# Joy2PS2_Adapter.net
KiCad netlist of a schematic drawn in EAGLE
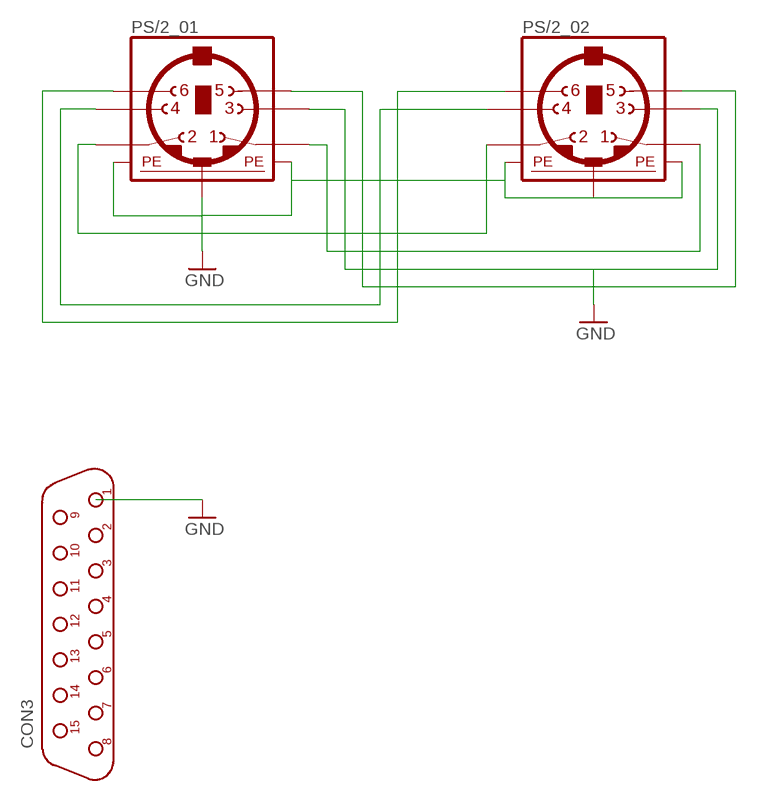
[diagram p0: schematic, sheet 1]

(export (version "E")
  (design (tool "Eeschema 10.0.6"))
  (components
    (comp (ref "CON3")
      (value "DB15F/90")
      (footprint "eagle-import:D-15F_90")
      (libsource (lib "eagle-import") (part "DB15F/90"))
    )
    (comp (ref "PS/2_01")
      (value "MINI_DIN_6")
      (footprint "eagle-import:M_DIN6")
      (libsource (lib "eagle-import") (part "MINI_DIN_6"))
    )
    (comp (ref "PS/2_02")
      (value "MINI_DIN_6")
      (footprint "eagle-import:M_DIN6")
      (libsource (lib "eagle-import") (part "MINI_DIN_6"))
    )
  )
  (nets
    (net (code "1") (name "GND") (class "Default")
      (node (ref "CON3") (pin "1") (pinfunction "1_1") (pintype "passive"))
      (node (ref "PS/2_01") (pin "3") (pinfunction "3_3") (pintype "passive"))
      (node (ref "PS/2_01") (pin "SH1") (pinfunction "PE1_SH1") (pintype "power_in"))
      (node (ref "PS/2_01") (pin "SH2") (pinfunction "PE2_SH2") (pintype "power_in"))
      (node (ref "PS/2_01") (pin "SH3") (pinfunction "PE3_SH3") (pintype "power_in"))
      (node (ref "PS/2_02") (pin "3") (pinfunction "3_3") (pintype "passive"))
      (node (ref "PS/2_02") (pin "SH1") (pinfunction "PE1_SH1") (pintype "power_in"))
      (node (ref "PS/2_02") (pin "SH2") (pinfunction "PE2_SH2") (pintype "power_in"))
      (node (ref "PS/2_02") (pin "SH3") (pinfunction "PE3_SH3") (pintype "power_in"))
    )
    (net (code "2") (name "Net-(PS/2_01-Pad1)") (class "Default")
      (node (ref "PS/2_01") (pin "1") (pinfunction "1_1") (pintype "passive"))
      (node (ref "PS/2_02") (pin "1") (pinfunction "1_1") (pintype "passive"))
    )
    (net (code "3") (name "Net-(PS/2_01-Pad2)") (class "Default")
      (node (ref "PS/2_01") (pin "2") (pinfunction "2_2") (pintype "passive"))
      (node (ref "PS/2_02") (pin "2") (pinfunction "2_2") (pintype "passive"))
    )
    (net (code "4") (name "Net-(PS/2_01-Pad4)") (class "Default")
      (node (ref "PS/2_01") (pin "4") (pinfunction "4_4") (pintype "passive"))
      (node (ref "PS/2_02") (pin "4") (pinfunction "4_4") (pintype "passive"))
    )
    (net (code "5") (name "Net-(PS/2_01-Pad5)") (class "Default")
      (node (ref "PS/2_01") (pin "5") (pinfunction "5_5") (pintype "passive"))
      (node (ref "PS/2_02") (pin "5") (pinfunction "5_5") (pintype "passive"))
    )
    (net (code "6") (name "Net-(PS/2_01-Pad6)") (class "Default")
      (node (ref "PS/2_01") (pin "6") (pinfunction "6_6") (pintype "passive"))
      (node (ref "PS/2_02") (pin "6") (pinfunction "6_6") (pintype "passive"))
    )
    (net (code "7") (name "unconnected-(CON3-Pad2)") (class "Default")
      (node (ref "CON3") (pin "2") (pinfunction "2_2") (pintype "passive"))
    )
    (net (code "8") (name "unconnected-(CON3-Pad3)") (class "Default")
      (node (ref "CON3") (pin "3") (pinfunction "3_3") (pintype "passive"))
    )
    (net (code "9") (name "unconnected-(CON3-Pad4)") (class "Default")
      (node (ref "CON3") (pin "4") (pinfunction "4_4") (pintype "passive"))
    )
    (net (code "10") (name "unconnected-(CON3-Pad5)") (class "Default")
      (node (ref "CON3") (pin "5") (pinfunction "5_5") (pintype "passive"))
    )
    (net (code "11") (name "unconnected-(CON3-Pad6)") (class "Default")
      (node (ref "CON3") (pin "6") (pinfunction "6_6") (pintype "passive"))
    )
    (net (code "12") (name "unconnected-(CON3-Pad7)") (class "Default")
      (node (ref "CON3") (pin "7") (pinfunction "7_7") (pintype "passive"))
    )
    (net (code "13") (name "unconnected-(CON3-Pad8)") (class "Default")
      (node (ref "CON3") (pin "8") (pinfunction "8_8") (pintype "passive"))
    )
    (net (code "14") (name "unconnected-(CON3-Pad9)") (class "Default")
      (node (ref "CON3") (pin "9") (pinfunction "9_9") (pintype "passive"))
    )
    (net (code "15") (name "unconnected-(CON3-Pad10)") (class "Default")
      (node (ref "CON3") (pin "10") (pinfunction "10_10") (pintype "passive"))
    )
    (net (code "16") (name "unconnected-(CON3-Pad11)") (class "Default")
      (node (ref "CON3") (pin "11") (pinfunction "11_11") (pintype "passive"))
    )
    (net (code "17") (name "unconnected-(CON3-Pad12)") (class "Default")
      (node (ref "CON3") (pin "12") (pinfunction "12_12") (pintype "passive"))
    )
    (net (code "18") (name "unconnected-(CON3-Pad13)") (class "Default")
      (node (ref "CON3") (pin "13") (pinfunction "13_13") (pintype "passive"))
    )
    (net (code "19") (name "unconnected-(CON3-Pad14)") (class "Default")
      (node (ref "CON3") (pin "14") (pinfunction "14_14") (pintype "passive"))
    )
    (net (code "20") (name "unconnected-(CON3-Pad15)") (class "Default")
      (node (ref "CON3") (pin "15") (pinfunction "15_15") (pintype "passive"))
    )
  )
)
